# Antenne.net
KiCad netlist of a schematic drawn in Altium Designer
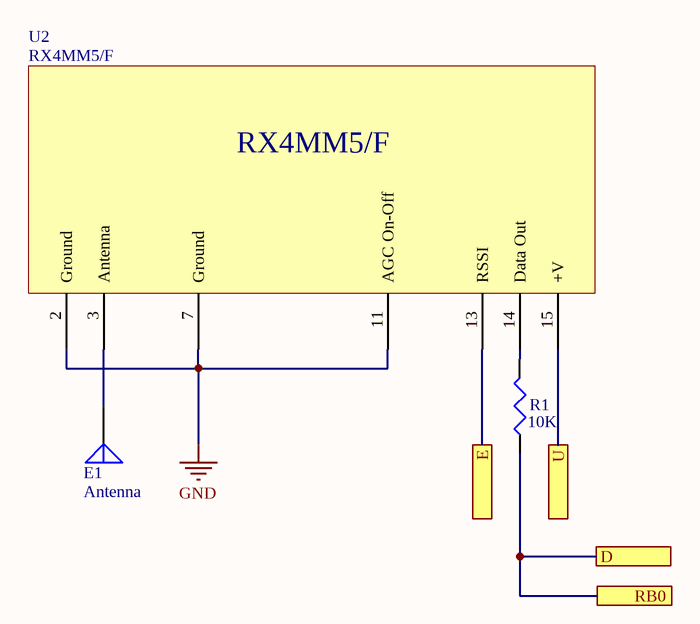
[diagram p0: Antenne.SchDoc]

(export (version "E")
  (design (tool "Eeschema 10.0.6"))
  (components
    (comp (ref "E1")
      (value "Antenna")
      (footprint "PIN1")
      (description "Generic Antenna")
      (fields (field (name "PUBLISHER") "Altium Limited"))
      (libsource (lib "Miscellaneous Devices") (part "Antenna"))
    )
    (comp (ref "R1")
      (value "10K")
      (footprint "J1-0603")
      (description "Resistor")
      (fields (field (name "Comment") "Res3") (field (name "PUBLISHER") "Altium Limited"))
      (libsource (lib "Miscellaneous Devices") (part "Res3"))
    )
    (comp (ref "U2")
      (value "RX4MM5/F")
      (footprint "RX4MM5/F")
      (description "RF Signal Receiver")
      (fields (field (name "PUBLISHER") "FJ Custom"))
      (libsource (lib "RF-Receiver") (part "RX4MM5/F"))
    )
  )
  (nets
    (net (code "1") (name "/D") (class "Default")
      (node (ref "R1") (pin "1") (pinfunction "1_1") (pintype "passive"))
    )
    (net (code "2") (name "/E") (class "Default")
      (node (ref "U2") (pin "13") (pinfunction "RSSI_13") (pintype "passive"))
    )
    (net (code "3") (name "/U") (class "Default")
      (node (ref "U2") (pin "15") (pinfunction "+V_15") (pintype "passive"))
    )
    (net (code "4") (name "GND") (class "Default")
      (node (ref "U2") (pin "11") (pinfunction "AGC_On-Off_11") (pintype "passive"))
      (node (ref "U2") (pin "2") (pinfunction "Ground_2") (pintype "passive"))
      (node (ref "U2") (pin "7") (pinfunction "Ground_7") (pintype "passive"))
    )
    (net (code "5") (name "Net-(E1-A)") (class "Default")
      (node (ref "E1") (pin "1") (pinfunction "A_1") (pintype "passive"))
      (node (ref "U2") (pin "3") (pinfunction "Antenna_3") (pintype "passive"))
    )
    (net (code "6") (name "Net-(U2-Data_Out)") (class "Default")
      (node (ref "R1") (pin "2") (pinfunction "2_2") (pintype "passive"))
      (node (ref "U2") (pin "14") (pinfunction "Data_Out_14") (pintype "passive"))
    )
  )
)
